# isolated-rj45-reva.net
KiCad netlist of a schematic drawn in EAGLE
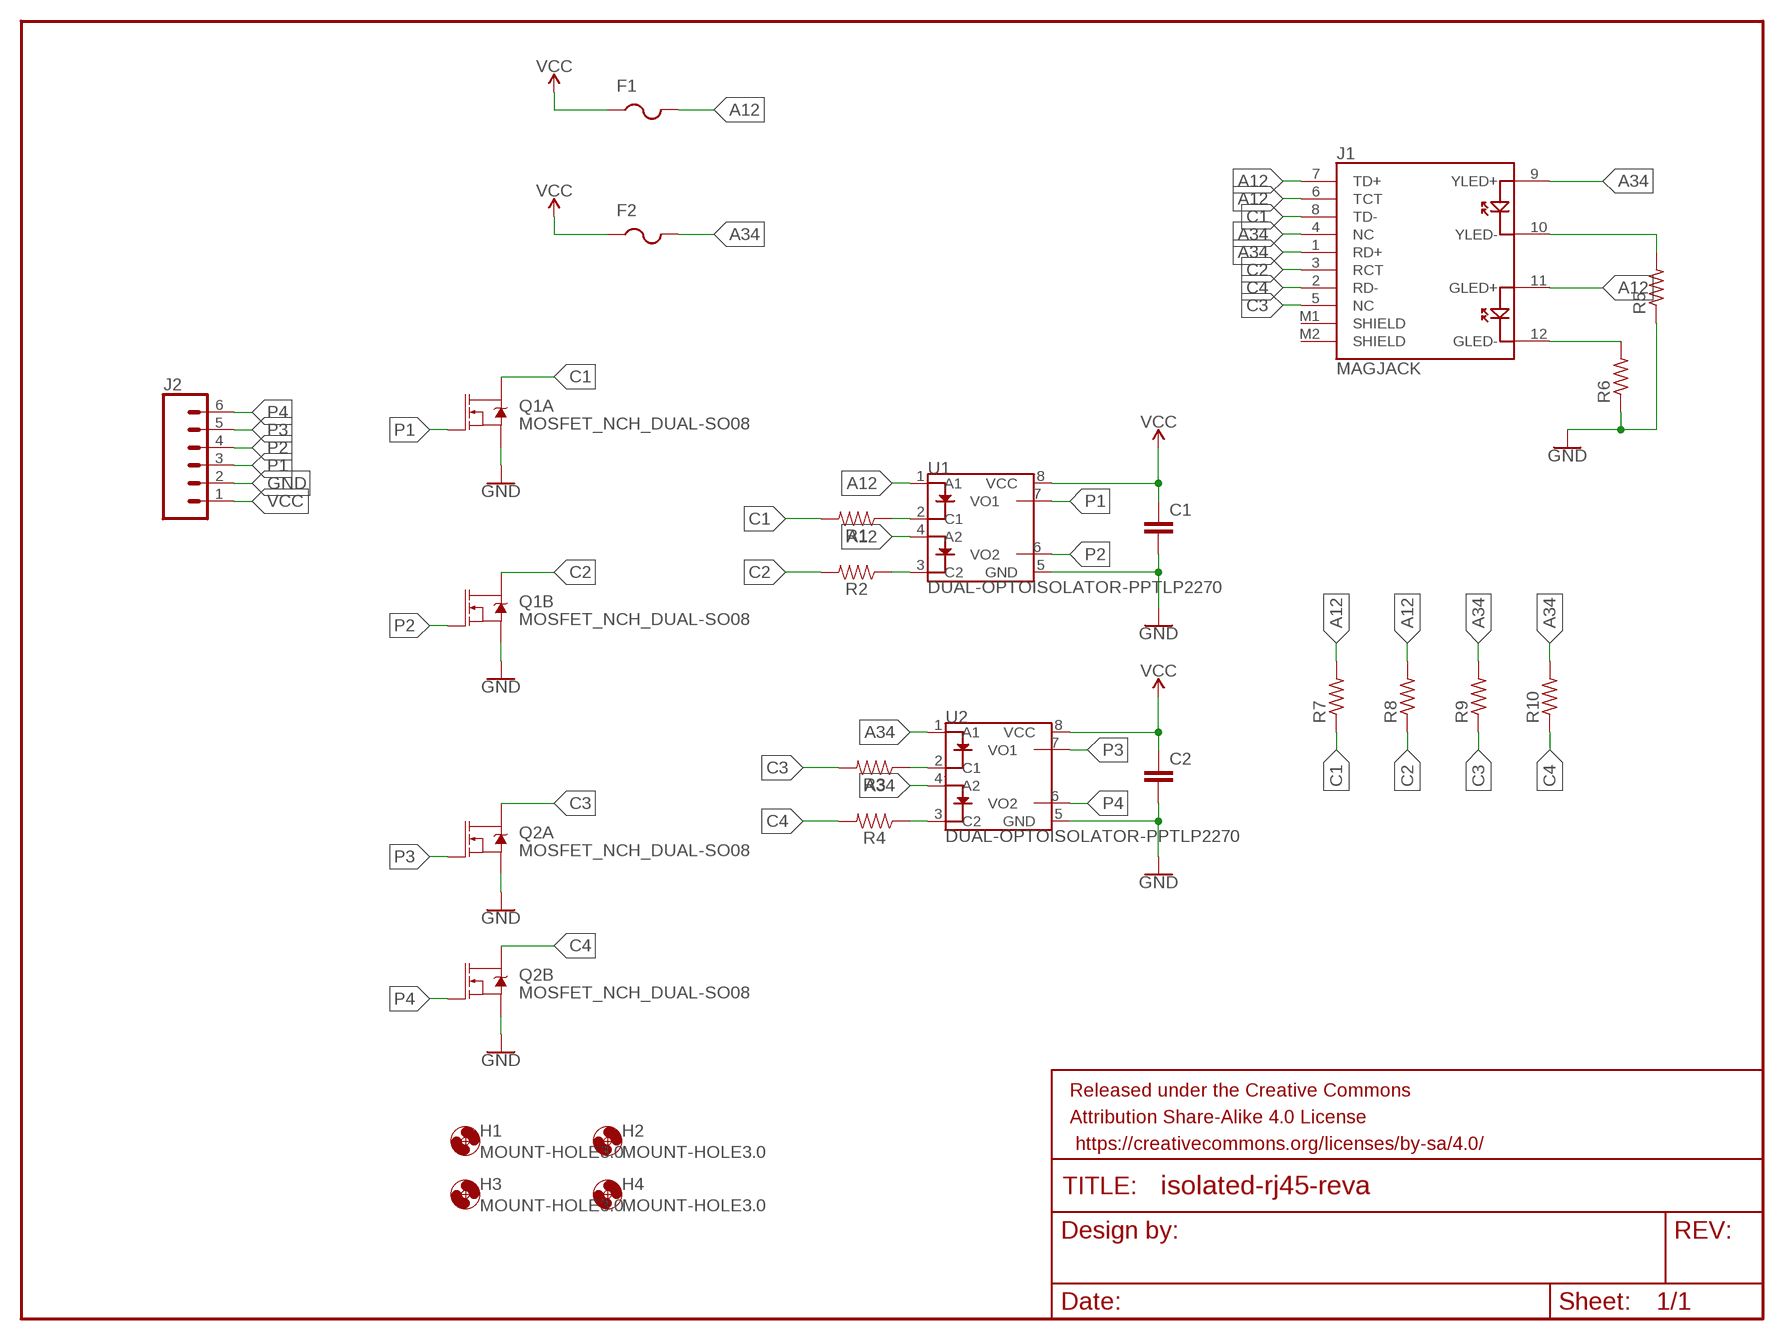
[diagram p0: schematic, sheet 1]

(export (version "E")
  (design (tool "Eeschema 10.0.6"))
  (components
    (comp (ref "C1")
      (value "CAPACITOR_0603_L")
      (footprint "eagle-import:RESC0603_L")
      (libsource (lib "eagle-import") (part "CAPACITOR_0603_L"))
    )
    (comp (ref "C2")
      (value "CAPACITOR_0603_L")
      (footprint "eagle-import:RESC0603_L")
      (libsource (lib "eagle-import") (part "CAPACITOR_0603_L"))
    )
    (comp (ref "F1")
      (value "PTCFUSE-1206")
      (footprint "eagle-import:R1206")
      (libsource (lib "eagle-import") (part "PTCFUSE-1206"))
    )
    (comp (ref "F2")
      (value "PTCFUSE-1206")
      (footprint "eagle-import:R1206")
      (libsource (lib "eagle-import") (part "PTCFUSE-1206"))
    )
    (comp (ref "FRAME1")
      (value "FRAME-LETTERNO_PACKAGE")
      (footprint "eagle-import:DUMMY")
      (fields (field (name "DESIGNER") "Nobody"))
      (libsource (lib "eagle-import") (part "FRAME-LETTERNO_PACKAGE"))
    )
    (comp (ref "H1")
      (value "MOUNT-HOLE3.0")
      (footprint "eagle-import:3,0")
      (libsource (lib "eagle-import") (part "MOUNT-HOLE3.0"))
    )
    (comp (ref "H2")
      (value "MOUNT-HOLE3.0")
      (footprint "eagle-import:3,0")
      (libsource (lib "eagle-import") (part "MOUNT-HOLE3.0"))
    )
    (comp (ref "H3")
      (value "MOUNT-HOLE3.0")
      (footprint "eagle-import:3,0")
      (libsource (lib "eagle-import") (part "MOUNT-HOLE3.0"))
    )
    (comp (ref "H4")
      (value "MOUNT-HOLE3.0")
      (footprint "eagle-import:3,0")
      (libsource (lib "eagle-import") (part "MOUNT-HOLE3.0"))
    )
    (comp (ref "J1")
      (value "MAGJACK")
      (footprint "eagle-import:MAGJACK")
      (libsource (lib "eagle-import") (part "MAGJACK"))
    )
    (comp (ref "J2")
      (value "CONN_06SILK_FEMALE_PTH")
      (footprint "eagle-import:1X06")
      (libsource (lib "eagle-import") (part "CONN_06SILK_FEMALE_PTH"))
    )
    (comp (ref "Q1")
      (value "MOSFET_NCH_DUAL-SO08")
      (footprint "eagle-import:SO08")
      (libsource (lib "eagle-import") (part "MOSFET_NCH_DUAL-SO08"))
    )
    (comp (ref "Q2")
      (value "MOSFET_NCH_DUAL-SO08")
      (footprint "eagle-import:SO08")
      (libsource (lib "eagle-import") (part "MOSFET_NCH_DUAL-SO08"))
    )
    (comp (ref "R1")
      (value "RESISTOR0603")
      (footprint "eagle-import:0603")
      (libsource (lib "eagle-import") (part "RESISTOR0603"))
    )
    (comp (ref "R2")
      (value "RESISTOR0603")
      (footprint "eagle-import:0603")
      (libsource (lib "eagle-import") (part "RESISTOR0603"))
    )
    (comp (ref "R3")
      (value "RESISTOR0603")
      (footprint "eagle-import:0603")
      (libsource (lib "eagle-import") (part "RESISTOR0603"))
    )
    (comp (ref "R4")
      (value "RESISTOR0603")
      (footprint "eagle-import:0603")
      (libsource (lib "eagle-import") (part "RESISTOR0603"))
    )
    (comp (ref "R5")
      (value "R-US_R0603")
      (footprint "eagle-import:R0603")
      (libsource (lib "eagle-import") (part "R-US_R0603"))
    )
    (comp (ref "R6")
      (value "R-US_R0603")
      (footprint "eagle-import:R0603")
      (libsource (lib "eagle-import") (part "R-US_R0603"))
    )
    (comp (ref "R7")
      (value "R-US_R0603")
      (footprint "eagle-import:R0603")
      (libsource (lib "eagle-import") (part "R-US_R0603"))
    )
    (comp (ref "R8")
      (value "R-US_R0603")
      (footprint "eagle-import:R0603")
      (libsource (lib "eagle-import") (part "R-US_R0603"))
    )
    (comp (ref "R9")
      (value "R-US_R0603")
      (footprint "eagle-import:R0603")
      (libsource (lib "eagle-import") (part "R-US_R0603"))
    )
    (comp (ref "R10")
      (value "R-US_R0603")
      (footprint "eagle-import:R0603")
      (libsource (lib "eagle-import") (part "R-US_R0603"))
    )
    (comp (ref "U1")
      (value "DUAL-OPTOISOLATOR-PPTLP2270")
      (footprint "eagle-import:11-6B1A")
      (libsource (lib "eagle-import") (part "DUAL-OPTOISOLATOR-PPTLP2270"))
    )
    (comp (ref "U2")
      (value "DUAL-OPTOISOLATOR-PPTLP2270")
      (footprint "eagle-import:11-6B1A")
      (libsource (lib "eagle-import") (part "DUAL-OPTOISOLATOR-PPTLP2270"))
    )
  )
  (nets
    (net (code "1") (name "A12") (class "Default")
      (node (ref "F1") (pin "2") (pinfunction "2_2") (pintype "passive"))
      (node (ref "J1") (pin "11") (pinfunction "GLED+_11") (pintype "bidirectional"))
      (node (ref "J1") (pin "6") (pinfunction "TCT_6") (pintype "bidirectional"))
      (node (ref "J1") (pin "7") (pinfunction "TD+_7") (pintype "bidirectional"))
      (node (ref "R7") (pin "2") (pinfunction "2_2") (pintype "passive"))
      (node (ref "R8") (pin "2") (pinfunction "2_2") (pintype "passive"))
      (node (ref "U1") (pin "1") (pinfunction "A1_1") (pintype "bidirectional"))
      (node (ref "U1") (pin "4") (pinfunction "A2_4") (pintype "bidirectional"))
    )
    (net (code "2") (name "A34") (class "Default")
      (node (ref "F2") (pin "2") (pinfunction "2_2") (pintype "passive"))
      (node (ref "J1") (pin "1") (pinfunction "RD+_1") (pintype "bidirectional"))
      (node (ref "J1") (pin "4") (pinfunction "NC_4") (pintype "bidirectional"))
      (node (ref "J1") (pin "9") (pinfunction "YLED+_9") (pintype "bidirectional"))
      (node (ref "R10") (pin "2") (pinfunction "2_2") (pintype "passive"))
      (node (ref "R9") (pin "2") (pinfunction "2_2") (pintype "passive"))
      (node (ref "U2") (pin "1") (pinfunction "A1_1") (pintype "bidirectional"))
      (node (ref "U2") (pin "4") (pinfunction "A2_4") (pintype "bidirectional"))
    )
    (net (code "3") (name "C1") (class "Default")
      (node (ref "J1") (pin "8") (pinfunction "TD-_8") (pintype "bidirectional"))
      (node (ref "Q1") (pin "7") (pinfunction "D_7") (pintype "bidirectional"))
      (node (ref "Q1") (pin "8") (pinfunction "D_8") (pintype "bidirectional"))
      (node (ref "R1") (pin "2") (pinfunction "2_2") (pintype "passive"))
      (node (ref "R7") (pin "1") (pinfunction "1_1") (pintype "passive"))
    )
    (net (code "4") (name "C2") (class "Default")
      (node (ref "J1") (pin "3") (pinfunction "RCT_3") (pintype "bidirectional"))
      (node (ref "Q1") (pin "5") (pinfunction "D_5") (pintype "bidirectional"))
      (node (ref "Q1") (pin "6") (pinfunction "D_6") (pintype "bidirectional"))
      (node (ref "R2") (pin "2") (pinfunction "2_2") (pintype "passive"))
      (node (ref "R8") (pin "1") (pinfunction "1_1") (pintype "passive"))
    )
    (net (code "5") (name "C3") (class "Default")
      (node (ref "J1") (pin "5") (pinfunction "NC_5") (pintype "bidirectional"))
      (node (ref "Q2") (pin "7") (pinfunction "D_7") (pintype "bidirectional"))
      (node (ref "Q2") (pin "8") (pinfunction "D_8") (pintype "bidirectional"))
      (node (ref "R3") (pin "2") (pinfunction "2_2") (pintype "passive"))
      (node (ref "R9") (pin "1") (pinfunction "1_1") (pintype "passive"))
    )
    (net (code "6") (name "C4") (class "Default")
      (node (ref "J1") (pin "2") (pinfunction "RD-_2") (pintype "bidirectional"))
      (node (ref "Q2") (pin "5") (pinfunction "D_5") (pintype "bidirectional"))
      (node (ref "Q2") (pin "6") (pinfunction "D_6") (pintype "bidirectional"))
      (node (ref "R10") (pin "1") (pinfunction "1_1") (pintype "passive"))
      (node (ref "R4") (pin "2") (pinfunction "2_2") (pintype "passive"))
    )
    (net (code "7") (name "GND") (class "Default")
      (node (ref "C1") (pin "2") (pinfunction "2_2") (pintype "passive"))
      (node (ref "C2") (pin "2") (pinfunction "2_2") (pintype "passive"))
      (node (ref "J2") (pin "2") (pinfunction "2_2") (pintype "passive"))
      (node (ref "Q1") (pin "1") (pinfunction "S_1") (pintype "bidirectional"))
      (node (ref "Q1") (pin "3") (pinfunction "S_3") (pintype "bidirectional"))
      (node (ref "Q2") (pin "1") (pinfunction "S_1") (pintype "bidirectional"))
      (node (ref "Q2") (pin "3") (pinfunction "S_3") (pintype "bidirectional"))
      (node (ref "R5") (pin "1") (pinfunction "1_1") (pintype "passive"))
      (node (ref "R6") (pin "1") (pinfunction "1_1") (pintype "passive"))
      (node (ref "U1") (pin "5") (pinfunction "GND_5") (pintype "bidirectional"))
      (node (ref "U2") (pin "5") (pinfunction "GND_5") (pintype "bidirectional"))
    )
    (net (code "8") (name "Net-(J1-GLED-)") (class "Default")
      (node (ref "J1") (pin "12") (pinfunction "GLED-_12") (pintype "bidirectional"))
      (node (ref "R6") (pin "2") (pinfunction "2_2") (pintype "passive"))
    )
    (net (code "9") (name "Net-(J1-YLED-)") (class "Default")
      (node (ref "J1") (pin "10") (pinfunction "YLED-_10") (pintype "bidirectional"))
      (node (ref "R5") (pin "2") (pinfunction "2_2") (pintype "passive"))
    )
    (net (code "10") (name "Net-(U1-C1)") (class "Default")
      (node (ref "R1") (pin "1") (pinfunction "1_1") (pintype "passive"))
      (node (ref "U1") (pin "2") (pinfunction "C1_2") (pintype "bidirectional"))
    )
    (net (code "11") (name "Net-(U1-C2)") (class "Default")
      (node (ref "R2") (pin "1") (pinfunction "1_1") (pintype "passive"))
      (node (ref "U1") (pin "3") (pinfunction "C2_3") (pintype "bidirectional"))
    )
    (net (code "12") (name "Net-(U2-C1)") (class "Default")
      (node (ref "R3") (pin "1") (pinfunction "1_1") (pintype "passive"))
      (node (ref "U2") (pin "2") (pinfunction "C1_2") (pintype "bidirectional"))
    )
    (net (code "13") (name "Net-(U2-C2)") (class "Default")
      (node (ref "R4") (pin "1") (pinfunction "1_1") (pintype "passive"))
      (node (ref "U2") (pin "3") (pinfunction "C2_3") (pintype "bidirectional"))
    )
    (net (code "14") (name "P1") (class "Default")
      (node (ref "J2") (pin "3") (pinfunction "3_3") (pintype "passive"))
      (node (ref "Q1") (pin "2") (pinfunction "G_2") (pintype "bidirectional"))
      (node (ref "U1") (pin "7") (pinfunction "VO1_7") (pintype "bidirectional"))
    )
    (net (code "15") (name "P2") (class "Default")
      (node (ref "J2") (pin "4") (pinfunction "4_4") (pintype "passive"))
      (node (ref "Q1") (pin "4") (pinfunction "G_4") (pintype "bidirectional"))
      (node (ref "U1") (pin "6") (pinfunction "VO2_6") (pintype "bidirectional"))
    )
    (net (code "16") (name "P3") (class "Default")
      (node (ref "J2") (pin "5") (pinfunction "5_5") (pintype "passive"))
      (node (ref "Q2") (pin "2") (pinfunction "G_2") (pintype "bidirectional"))
      (node (ref "U2") (pin "7") (pinfunction "VO1_7") (pintype "bidirectional"))
    )
    (net (code "17") (name "P4") (class "Default")
      (node (ref "J2") (pin "6") (pinfunction "6_6") (pintype "passive"))
      (node (ref "Q2") (pin "4") (pinfunction "G_4") (pintype "bidirectional"))
      (node (ref "U2") (pin "6") (pinfunction "VO2_6") (pintype "bidirectional"))
    )
    (net (code "18") (name "VCC") (class "Default")
      (node (ref "C1") (pin "1") (pinfunction "1_1") (pintype "passive"))
      (node (ref "C2") (pin "1") (pinfunction "1_1") (pintype "passive"))
      (node (ref "F1") (pin "1") (pinfunction "1_1") (pintype "passive"))
      (node (ref "F2") (pin "1") (pinfunction "1_1") (pintype "passive"))
      (node (ref "J2") (pin "1") (pinfunction "1_1") (pintype "passive"))
      (node (ref "U1") (pin "8") (pinfunction "VCC_8") (pintype "bidirectional"))
      (node (ref "U2") (pin "8") (pinfunction "VCC_8") (pintype "bidirectional"))
    )
    (net (code "19") (name "unconnected-(J1-SHIELD-PadM1)") (class "Default")
      (node (ref "J1") (pin "M1") (pinfunction "SHIELD_M1") (pintype "bidirectional"))
    )
    (net (code "20") (name "unconnected-(J1-SHIELD-PadM2)") (class "Default")
      (node (ref "J1") (pin "M2") (pinfunction "SHIELD_M2") (pintype "bidirectional"))
    )
  )
)
